# StackBreakoutConnection_4layers_V1_0.net
KiCad netlist of a schematic drawn in EAGLE
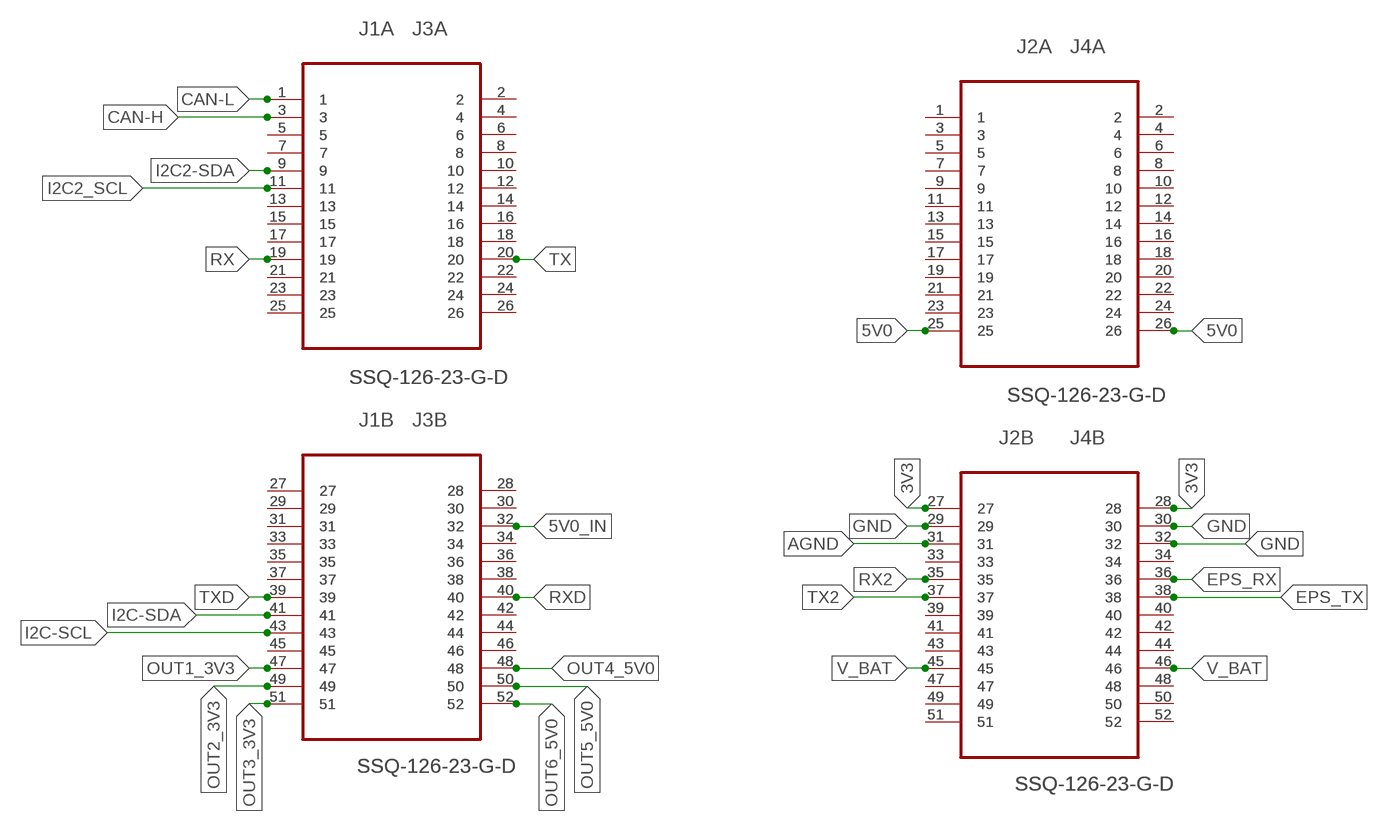
[diagram p0: schematic, sheet 1]

(export (version "E")
  (design (tool "Eeschema 10.0.6"))
  (components
    (comp (ref "J1")
      (value "SSQ-126-23-G-D")
      (footprint "eagle-import:SAMTEC_SSQ-126-23-G-D")
      (libsource (lib "eagle-import") (part "SSQ-126-23-G-D"))
    )
    (comp (ref "J2")
      (value "SSQ-126-23-G-D")
      (footprint "eagle-import:SAMTEC_SSQ-126-23-G-D")
      (libsource (lib "eagle-import") (part "SSQ-126-23-G-D"))
    )
    (comp (ref "J3")
      (value "SSQ-126-23-G-D")
      (footprint "eagle-import:SAMTEC_SSQ-126-23-G-D")
      (libsource (lib "eagle-import") (part "SSQ-126-23-G-D"))
    )
    (comp (ref "J4")
      (value "SSQ-126-23-G-D")
      (footprint "eagle-import:SAMTEC_SSQ-126-23-G-D")
      (libsource (lib "eagle-import") (part "SSQ-126-23-G-D"))
    )
  )
  (nets
    (net (code "1") (name "3V3") (class "Default")
      (node (ref "J2") (pin "27") (pinfunction "27_27") (pintype "passive"))
      (node (ref "J2") (pin "28") (pinfunction "28_28") (pintype "passive"))
      (node (ref "J4") (pin "27") (pinfunction "27_27") (pintype "passive"))
      (node (ref "J4") (pin "28") (pinfunction "28_28") (pintype "passive"))
    )
    (net (code "2") (name "5V0") (class "Default")
      (node (ref "J2") (pin "25") (pinfunction "25_25") (pintype "passive"))
      (node (ref "J2") (pin "26") (pinfunction "26_26") (pintype "passive"))
      (node (ref "J4") (pin "25") (pinfunction "25_25") (pintype "passive"))
      (node (ref "J4") (pin "26") (pinfunction "26_26") (pintype "passive"))
    )
    (net (code "3") (name "5V0_IN") (class "Default")
      (node (ref "J1") (pin "32") (pinfunction "32_32") (pintype "passive"))
      (node (ref "J3") (pin "32") (pinfunction "32_32") (pintype "passive"))
    )
    (net (code "4") (name "AGND") (class "Default")
      (node (ref "J2") (pin "31") (pinfunction "31_31") (pintype "passive"))
      (node (ref "J4") (pin "31") (pinfunction "31_31") (pintype "passive"))
    )
    (net (code "5") (name "CAN-H") (class "Default")
      (node (ref "J1") (pin "3") (pinfunction "3_3") (pintype "passive"))
      (node (ref "J3") (pin "3") (pinfunction "3_3") (pintype "passive"))
    )
    (net (code "6") (name "CAN-L") (class "Default")
      (node (ref "J1") (pin "1") (pinfunction "1_1") (pintype "passive"))
      (node (ref "J3") (pin "1") (pinfunction "1_1") (pintype "passive"))
    )
    (net (code "7") (name "EPS_RX") (class "Default")
      (node (ref "J2") (pin "36") (pinfunction "36_36") (pintype "passive"))
      (node (ref "J4") (pin "36") (pinfunction "36_36") (pintype "passive"))
    )
    (net (code "8") (name "EPS_TX") (class "Default")
      (node (ref "J2") (pin "38") (pinfunction "38_38") (pintype "passive"))
      (node (ref "J4") (pin "38") (pinfunction "38_38") (pintype "passive"))
    )
    (net (code "9") (name "GND") (class "Default")
      (node (ref "J2") (pin "29") (pinfunction "29_29") (pintype "passive"))
      (node (ref "J2") (pin "30") (pinfunction "30_30") (pintype "passive"))
      (node (ref "J2") (pin "32") (pinfunction "32_32") (pintype "passive"))
      (node (ref "J4") (pin "29") (pinfunction "29_29") (pintype "passive"))
      (node (ref "J4") (pin "30") (pinfunction "30_30") (pintype "passive"))
      (node (ref "J4") (pin "32") (pinfunction "32_32") (pintype "passive"))
    )
    (net (code "10") (name "I2C-SCL") (class "Default")
      (node (ref "J1") (pin "43") (pinfunction "43_43") (pintype "passive"))
      (node (ref "J3") (pin "43") (pinfunction "43_43") (pintype "passive"))
    )
    (net (code "11") (name "I2C-SDA") (class "Default")
      (node (ref "J1") (pin "41") (pinfunction "41_41") (pintype "passive"))
      (node (ref "J3") (pin "41") (pinfunction "41_41") (pintype "passive"))
    )
    (net (code "12") (name "I2C2-SDA") (class "Default")
      (node (ref "J1") (pin "9") (pinfunction "9_9") (pintype "passive"))
      (node (ref "J3") (pin "9") (pinfunction "9_9") (pintype "passive"))
    )
    (net (code "13") (name "I2C2_SCL") (class "Default")
      (node (ref "J1") (pin "11") (pinfunction "11_11") (pintype "passive"))
      (node (ref "J3") (pin "11") (pinfunction "11_11") (pintype "passive"))
    )
    (net (code "14") (name "Net-(J1-Pad2)") (class "Default")
      (node (ref "J1") (pin "2") (pinfunction "2_2") (pintype "passive"))
      (node (ref "J3") (pin "2") (pinfunction "2_2") (pintype "passive"))
    )
    (net (code "15") (name "Net-(J1-Pad4)") (class "Default")
      (node (ref "J1") (pin "4") (pinfunction "4_4") (pintype "passive"))
      (node (ref "J3") (pin "4") (pinfunction "4_4") (pintype "passive"))
    )
    (net (code "16") (name "Net-(J1-Pad5)") (class "Default")
      (node (ref "J1") (pin "5") (pinfunction "5_5") (pintype "passive"))
      (node (ref "J3") (pin "5") (pinfunction "5_5") (pintype "passive"))
    )
    (net (code "17") (name "Net-(J1-Pad6)") (class "Default")
      (node (ref "J1") (pin "6") (pinfunction "6_6") (pintype "passive"))
      (node (ref "J3") (pin "6") (pinfunction "6_6") (pintype "passive"))
    )
    (net (code "18") (name "Net-(J1-Pad7)") (class "Default")
      (node (ref "J1") (pin "7") (pinfunction "7_7") (pintype "passive"))
      (node (ref "J3") (pin "7") (pinfunction "7_7") (pintype "passive"))
    )
    (net (code "19") (name "Net-(J1-Pad8)") (class "Default")
      (node (ref "J1") (pin "8") (pinfunction "8_8") (pintype "passive"))
      (node (ref "J3") (pin "8") (pinfunction "8_8") (pintype "passive"))
    )
    (net (code "20") (name "Net-(J1-Pad10)") (class "Default")
      (node (ref "J1") (pin "10") (pinfunction "10_10") (pintype "passive"))
      (node (ref "J3") (pin "10") (pinfunction "10_10") (pintype "passive"))
    )
    (net (code "21") (name "Net-(J1-Pad12)") (class "Default")
      (node (ref "J1") (pin "12") (pinfunction "12_12") (pintype "passive"))
      (node (ref "J3") (pin "12") (pinfunction "12_12") (pintype "passive"))
    )
    (net (code "22") (name "Net-(J1-Pad13)") (class "Default")
      (node (ref "J1") (pin "13") (pinfunction "13_13") (pintype "passive"))
      (node (ref "J3") (pin "13") (pinfunction "13_13") (pintype "passive"))
    )
    (net (code "23") (name "Net-(J1-Pad14)") (class "Default")
      (node (ref "J1") (pin "14") (pinfunction "14_14") (pintype "passive"))
      (node (ref "J3") (pin "14") (pinfunction "14_14") (pintype "passive"))
    )
    (net (code "24") (name "Net-(J1-Pad15)") (class "Default")
      (node (ref "J1") (pin "15") (pinfunction "15_15") (pintype "passive"))
      (node (ref "J3") (pin "15") (pinfunction "15_15") (pintype "passive"))
    )
    (net (code "25") (name "Net-(J1-Pad16)") (class "Default")
      (node (ref "J1") (pin "16") (pinfunction "16_16") (pintype "passive"))
      (node (ref "J3") (pin "16") (pinfunction "16_16") (pintype "passive"))
    )
    (net (code "26") (name "Net-(J1-Pad17)") (class "Default")
      (node (ref "J1") (pin "17") (pinfunction "17_17") (pintype "passive"))
      (node (ref "J3") (pin "17") (pinfunction "17_17") (pintype "passive"))
    )
    (net (code "27") (name "Net-(J1-Pad18)") (class "Default")
      (node (ref "J1") (pin "18") (pinfunction "18_18") (pintype "passive"))
      (node (ref "J3") (pin "18") (pinfunction "18_18") (pintype "passive"))
    )
    (net (code "28") (name "Net-(J1-Pad21)") (class "Default")
      (node (ref "J1") (pin "21") (pinfunction "21_21") (pintype "passive"))
      (node (ref "J3") (pin "21") (pinfunction "21_21") (pintype "passive"))
    )
    (net (code "29") (name "Net-(J1-Pad22)") (class "Default")
      (node (ref "J1") (pin "22") (pinfunction "22_22") (pintype "passive"))
      (node (ref "J3") (pin "22") (pinfunction "22_22") (pintype "passive"))
    )
    (net (code "30") (name "Net-(J1-Pad23)") (class "Default")
      (node (ref "J1") (pin "23") (pinfunction "23_23") (pintype "passive"))
      (node (ref "J3") (pin "23") (pinfunction "23_23") (pintype "passive"))
    )
    (net (code "31") (name "Net-(J1-Pad24)") (class "Default")
      (node (ref "J1") (pin "24") (pinfunction "24_24") (pintype "passive"))
      (node (ref "J3") (pin "24") (pinfunction "24_24") (pintype "passive"))
    )
    (net (code "32") (name "Net-(J1-Pad25)") (class "Default")
      (node (ref "J1") (pin "25") (pinfunction "25_25") (pintype "passive"))
      (node (ref "J3") (pin "25") (pinfunction "25_25") (pintype "passive"))
    )
    (net (code "33") (name "Net-(J1-Pad26)") (class "Default")
      (node (ref "J1") (pin "26") (pinfunction "26_26") (pintype "passive"))
      (node (ref "J3") (pin "26") (pinfunction "26_26") (pintype "passive"))
    )
    (net (code "34") (name "Net-(J1-Pad27)") (class "Default")
      (node (ref "J1") (pin "27") (pinfunction "27_27") (pintype "passive"))
      (node (ref "J3") (pin "27") (pinfunction "27_27") (pintype "passive"))
    )
    (net (code "35") (name "Net-(J1-Pad28)") (class "Default")
      (node (ref "J1") (pin "28") (pinfunction "28_28") (pintype "passive"))
      (node (ref "J3") (pin "28") (pinfunction "28_28") (pintype "passive"))
    )
    (net (code "36") (name "Net-(J1-Pad29)") (class "Default")
      (node (ref "J1") (pin "29") (pinfunction "29_29") (pintype "passive"))
      (node (ref "J3") (pin "29") (pinfunction "29_29") (pintype "passive"))
    )
    (net (code "37") (name "Net-(J1-Pad30)") (class "Default")
      (node (ref "J1") (pin "30") (pinfunction "30_30") (pintype "passive"))
      (node (ref "J3") (pin "30") (pinfunction "30_30") (pintype "passive"))
    )
    (net (code "38") (name "Net-(J1-Pad31)") (class "Default")
      (node (ref "J1") (pin "31") (pinfunction "31_31") (pintype "passive"))
      (node (ref "J3") (pin "31") (pinfunction "31_31") (pintype "passive"))
    )
    (net (code "39") (name "Net-(J1-Pad33)") (class "Default")
      (node (ref "J1") (pin "33") (pinfunction "33_33") (pintype "passive"))
      (node (ref "J3") (pin "33") (pinfunction "33_33") (pintype "passive"))
    )
    (net (code "40") (name "Net-(J1-Pad34)") (class "Default")
      (node (ref "J1") (pin "34") (pinfunction "34_34") (pintype "passive"))
      (node (ref "J3") (pin "34") (pinfunction "34_34") (pintype "passive"))
    )
    (net (code "41") (name "Net-(J1-Pad35)") (class "Default")
      (node (ref "J1") (pin "35") (pinfunction "35_35") (pintype "passive"))
      (node (ref "J3") (pin "35") (pinfunction "35_35") (pintype "passive"))
    )
    (net (code "42") (name "Net-(J1-Pad36)") (class "Default")
      (node (ref "J1") (pin "36") (pinfunction "36_36") (pintype "passive"))
      (node (ref "J3") (pin "36") (pinfunction "36_36") (pintype "passive"))
    )
    (net (code "43") (name "Net-(J1-Pad37)") (class "Default")
      (node (ref "J1") (pin "37") (pinfunction "37_37") (pintype "passive"))
      (node (ref "J3") (pin "37") (pinfunction "37_37") (pintype "passive"))
    )
    (net (code "44") (name "Net-(J1-Pad38)") (class "Default")
      (node (ref "J1") (pin "38") (pinfunction "38_38") (pintype "passive"))
      (node (ref "J3") (pin "38") (pinfunction "38_38") (pintype "passive"))
    )
    (net (code "45") (name "Net-(J1-Pad42)") (class "Default")
      (node (ref "J1") (pin "42") (pinfunction "42_42") (pintype "passive"))
      (node (ref "J3") (pin "42") (pinfunction "42_42") (pintype "passive"))
    )
    (net (code "46") (name "Net-(J1-Pad44)") (class "Default")
      (node (ref "J1") (pin "44") (pinfunction "44_44") (pintype "passive"))
      (node (ref "J3") (pin "44") (pinfunction "44_44") (pintype "passive"))
    )
    (net (code "47") (name "Net-(J1-Pad45)") (class "Default")
      (node (ref "J1") (pin "45") (pinfunction "45_45") (pintype "passive"))
      (node (ref "J3") (pin "45") (pinfunction "45_45") (pintype "passive"))
    )
    (net (code "48") (name "Net-(J1-Pad46)") (class "Default")
      (node (ref "J1") (pin "46") (pinfunction "46_46") (pintype "passive"))
      (node (ref "J3") (pin "46") (pinfunction "46_46") (pintype "passive"))
    )
    (net (code "49") (name "Net-(J2-Pad1)") (class "Default")
      (node (ref "J2") (pin "1") (pinfunction "1_1") (pintype "passive"))
      (node (ref "J4") (pin "1") (pinfunction "1_1") (pintype "passive"))
    )
    (net (code "50") (name "Net-(J2-Pad2)") (class "Default")
      (node (ref "J2") (pin "2") (pinfunction "2_2") (pintype "passive"))
      (node (ref "J4") (pin "2") (pinfunction "2_2") (pintype "passive"))
    )
    (net (code "51") (name "Net-(J2-Pad3)") (class "Default")
      (node (ref "J2") (pin "3") (pinfunction "3_3") (pintype "passive"))
      (node (ref "J4") (pin "3") (pinfunction "3_3") (pintype "passive"))
    )
    (net (code "52") (name "Net-(J2-Pad4)") (class "Default")
      (node (ref "J2") (pin "4") (pinfunction "4_4") (pintype "passive"))
      (node (ref "J4") (pin "4") (pinfunction "4_4") (pintype "passive"))
    )
    (net (code "53") (name "Net-(J2-Pad5)") (class "Default")
      (node (ref "J2") (pin "5") (pinfunction "5_5") (pintype "passive"))
      (node (ref "J4") (pin "5") (pinfunction "5_5") (pintype "passive"))
    )
    (net (code "54") (name "Net-(J2-Pad6)") (class "Default")
      (node (ref "J2") (pin "6") (pinfunction "6_6") (pintype "passive"))
      (node (ref "J4") (pin "6") (pinfunction "6_6") (pintype "passive"))
    )
    (net (code "55") (name "Net-(J2-Pad7)") (class "Default")
      (node (ref "J2") (pin "7") (pinfunction "7_7") (pintype "passive"))
      (node (ref "J4") (pin "7") (pinfunction "7_7") (pintype "passive"))
    )
    (net (code "56") (name "Net-(J2-Pad8)") (class "Default")
      (node (ref "J2") (pin "8") (pinfunction "8_8") (pintype "passive"))
      (node (ref "J4") (pin "8") (pinfunction "8_8") (pintype "passive"))
    )
    (net (code "57") (name "Net-(J2-Pad9)") (class "Default")
      (node (ref "J2") (pin "9") (pinfunction "9_9") (pintype "passive"))
      (node (ref "J4") (pin "9") (pinfunction "9_9") (pintype "passive"))
    )
    (net (code "58") (name "Net-(J2-Pad10)") (class "Default")
      (node (ref "J2") (pin "10") (pinfunction "10_10") (pintype "passive"))
      (node (ref "J4") (pin "10") (pinfunction "10_10") (pintype "passive"))
    )
    (net (code "59") (name "Net-(J2-Pad11)") (class "Default")
      (node (ref "J2") (pin "11") (pinfunction "11_11") (pintype "passive"))
      (node (ref "J4") (pin "11") (pinfunction "11_11") (pintype "passive"))
    )
    (net (code "60") (name "Net-(J2-Pad12)") (class "Default")
      (node (ref "J2") (pin "12") (pinfunction "12_12") (pintype "passive"))
      (node (ref "J4") (pin "12") (pinfunction "12_12") (pintype "passive"))
    )
    (net (code "61") (name "Net-(J2-Pad13)") (class "Default")
      (node (ref "J2") (pin "13") (pinfunction "13_13") (pintype "passive"))
      (node (ref "J4") (pin "13") (pinfunction "13_13") (pintype "passive"))
    )
    (net (code "62") (name "Net-(J2-Pad14)") (class "Default")
      (node (ref "J2") (pin "14") (pinfunction "14_14") (pintype "passive"))
      (node (ref "J4") (pin "14") (pinfunction "14_14") (pintype "passive"))
    )
    (net (code "63") (name "Net-(J2-Pad15)") (class "Default")
      (node (ref "J2") (pin "15") (pinfunction "15_15") (pintype "passive"))
      (node (ref "J4") (pin "15") (pinfunction "15_15") (pintype "passive"))
    )
    (net (code "64") (name "Net-(J2-Pad16)") (class "Default")
      (node (ref "J2") (pin "16") (pinfunction "16_16") (pintype "passive"))
      (node (ref "J4") (pin "16") (pinfunction "16_16") (pintype "passive"))
    )
    (net (code "65") (name "Net-(J2-Pad17)") (class "Default")
      (node (ref "J2") (pin "17") (pinfunction "17_17") (pintype "passive"))
      (node (ref "J4") (pin "17") (pinfunction "17_17") (pintype "passive"))
    )
    (net (code "66") (name "Net-(J2-Pad18)") (class "Default")
      (node (ref "J2") (pin "18") (pinfunction "18_18") (pintype "passive"))
      (node (ref "J4") (pin "18") (pinfunction "18_18") (pintype "passive"))
    )
    (net (code "67") (name "Net-(J2-Pad19)") (class "Default")
      (node (ref "J2") (pin "19") (pinfunction "19_19") (pintype "passive"))
      (node (ref "J4") (pin "19") (pinfunction "19_19") (pintype "passive"))
    )
    (net (code "68") (name "Net-(J2-Pad20)") (class "Default")
      (node (ref "J2") (pin "20") (pinfunction "20_20") (pintype "passive"))
      (node (ref "J4") (pin "20") (pinfunction "20_20") (pintype "passive"))
    )
    (net (code "69") (name "Net-(J2-Pad21)") (class "Default")
      (node (ref "J2") (pin "21") (pinfunction "21_21") (pintype "passive"))
      (node (ref "J4") (pin "21") (pinfunction "21_21") (pintype "passive"))
    )
    (net (code "70") (name "Net-(J2-Pad22)") (class "Default")
      (node (ref "J2") (pin "22") (pinfunction "22_22") (pintype "passive"))
      (node (ref "J4") (pin "22") (pinfunction "22_22") (pintype "passive"))
    )
    (net (code "71") (name "Net-(J2-Pad23)") (class "Default")
      (node (ref "J2") (pin "23") (pinfunction "23_23") (pintype "passive"))
      (node (ref "J4") (pin "23") (pinfunction "23_23") (pintype "passive"))
    )
    (net (code "72") (name "Net-(J2-Pad24)") (class "Default")
      (node (ref "J2") (pin "24") (pinfunction "24_24") (pintype "passive"))
      (node (ref "J4") (pin "24") (pinfunction "24_24") (pintype "passive"))
    )
    (net (code "73") (name "Net-(J2-Pad33)") (class "Default")
      (node (ref "J2") (pin "33") (pinfunction "33_33") (pintype "passive"))
      (node (ref "J4") (pin "33") (pinfunction "33_33") (pintype "passive"))
    )
    (net (code "74") (name "Net-(J2-Pad34)") (class "Default")
      (node (ref "J2") (pin "34") (pinfunction "34_34") (pintype "passive"))
      (node (ref "J4") (pin "34") (pinfunction "34_34") (pintype "passive"))
    )
    (net (code "75") (name "Net-(J2-Pad39)") (class "Default")
      (node (ref "J2") (pin "39") (pinfunction "39_39") (pintype "passive"))
      (node (ref "J4") (pin "39") (pinfunction "39_39") (pintype "passive"))
    )
    (net (code "76") (name "Net-(J2-Pad40)") (class "Default")
      (node (ref "J2") (pin "40") (pinfunction "40_40") (pintype "passive"))
      (node (ref "J4") (pin "40") (pinfunction "40_40") (pintype "passive"))
    )
    (net (code "77") (name "Net-(J2-Pad41)") (class "Default")
      (node (ref "J2") (pin "41") (pinfunction "41_41") (pintype "passive"))
      (node (ref "J4") (pin "41") (pinfunction "41_41") (pintype "passive"))
    )
    (net (code "78") (name "Net-(J2-Pad42)") (class "Default")
      (node (ref "J2") (pin "42") (pinfunction "42_42") (pintype "passive"))
      (node (ref "J4") (pin "42") (pinfunction "42_42") (pintype "passive"))
    )
    (net (code "79") (name "Net-(J2-Pad43)") (class "Default")
      (node (ref "J2") (pin "43") (pinfunction "43_43") (pintype "passive"))
      (node (ref "J4") (pin "43") (pinfunction "43_43") (pintype "passive"))
    )
    (net (code "80") (name "Net-(J2-Pad44)") (class "Default")
      (node (ref "J2") (pin "44") (pinfunction "44_44") (pintype "passive"))
      (node (ref "J4") (pin "44") (pinfunction "44_44") (pintype "passive"))
    )
    (net (code "81") (name "Net-(J2-Pad47)") (class "Default")
      (node (ref "J2") (pin "47") (pinfunction "47_47") (pintype "passive"))
      (node (ref "J4") (pin "47") (pinfunction "47_47") (pintype "passive"))
    )
    (net (code "82") (name "Net-(J2-Pad48)") (class "Default")
      (node (ref "J2") (pin "48") (pinfunction "48_48") (pintype "passive"))
      (node (ref "J4") (pin "48") (pinfunction "48_48") (pintype "passive"))
    )
    (net (code "83") (name "Net-(J2-Pad49)") (class "Default")
      (node (ref "J2") (pin "49") (pinfunction "49_49") (pintype "passive"))
      (node (ref "J4") (pin "49") (pinfunction "49_49") (pintype "passive"))
    )
    (net (code "84") (name "Net-(J2-Pad50)") (class "Default")
      (node (ref "J2") (pin "50") (pinfunction "50_50") (pintype "passive"))
      (node (ref "J4") (pin "50") (pinfunction "50_50") (pintype "passive"))
    )
    (net (code "85") (name "Net-(J2-Pad51)") (class "Default")
      (node (ref "J2") (pin "51") (pinfunction "51_51") (pintype "passive"))
      (node (ref "J4") (pin "51") (pinfunction "51_51") (pintype "passive"))
    )
    (net (code "86") (name "Net-(J2-Pad52)") (class "Default")
      (node (ref "J2") (pin "52") (pinfunction "52_52") (pintype "passive"))
      (node (ref "J4") (pin "52") (pinfunction "52_52") (pintype "passive"))
    )
    (net (code "87") (name "OUT1_3V3") (class "Default")
      (node (ref "J1") (pin "47") (pinfunction "47_47") (pintype "passive"))
      (node (ref "J3") (pin "47") (pinfunction "47_47") (pintype "passive"))
    )
    (net (code "88") (name "OUT2_3V3") (class "Default")
      (node (ref "J1") (pin "49") (pinfunction "49_49") (pintype "passive"))
      (node (ref "J3") (pin "49") (pinfunction "49_49") (pintype "passive"))
    )
    (net (code "89") (name "OUT3_3V3") (class "Default")
      (node (ref "J1") (pin "51") (pinfunction "51_51") (pintype "passive"))
      (node (ref "J3") (pin "51") (pinfunction "51_51") (pintype "passive"))
    )
    (net (code "90") (name "OUT4_5V0") (class "Default")
      (node (ref "J1") (pin "48") (pinfunction "48_48") (pintype "passive"))
      (node (ref "J3") (pin "48") (pinfunction "48_48") (pintype "passive"))
    )
    (net (code "91") (name "OUT5_5V0") (class "Default")
      (node (ref "J1") (pin "50") (pinfunction "50_50") (pintype "passive"))
      (node (ref "J3") (pin "50") (pinfunction "50_50") (pintype "passive"))
    )
    (net (code "92") (name "OUT6_5V0") (class "Default")
      (node (ref "J1") (pin "52") (pinfunction "52_52") (pintype "passive"))
      (node (ref "J3") (pin "52") (pinfunction "52_52") (pintype "passive"))
    )
    (net (code "93") (name "RX") (class "Default")
      (node (ref "J1") (pin "19") (pinfunction "19_19") (pintype "passive"))
      (node (ref "J3") (pin "19") (pinfunction "19_19") (pintype "passive"))
    )
    (net (code "94") (name "RX2") (class "Default")
      (node (ref "J2") (pin "35") (pinfunction "35_35") (pintype "passive"))
      (node (ref "J4") (pin "35") (pinfunction "35_35") (pintype "passive"))
    )
    (net (code "95") (name "RXD") (class "Default")
      (node (ref "J1") (pin "40") (pinfunction "40_40") (pintype "passive"))
      (node (ref "J3") (pin "40") (pinfunction "40_40") (pintype "passive"))
    )
    (net (code "96") (name "TX") (class "Default")
      (node (ref "J1") (pin "20") (pinfunction "20_20") (pintype "passive"))
      (node (ref "J3") (pin "20") (pinfunction "20_20") (pintype "passive"))
    )
    (net (code "97") (name "TX2") (class "Default")
      (node (ref "J2") (pin "37") (pinfunction "37_37") (pintype "passive"))
      (node (ref "J4") (pin "37") (pinfunction "37_37") (pintype "passive"))
    )
    (net (code "98") (name "TXD") (class "Default")
      (node (ref "J1") (pin "39") (pinfunction "39_39") (pintype "passive"))
      (node (ref "J3") (pin "39") (pinfunction "39_39") (pintype "passive"))
    )
    (net (code "99") (name "V_BAT") (class "Default")
      (node (ref "J2") (pin "45") (pinfunction "45_45") (pintype "passive"))
      (node (ref "J2") (pin "46") (pinfunction "46_46") (pintype "passive"))
      (node (ref "J4") (pin "45") (pinfunction "45_45") (pintype "passive"))
      (node (ref "J4") (pin "46") (pinfunction "46_46") (pintype "passive"))
    )
  )
)
